# USB-CB.net
KiCad netlist of a schematic drawn in EAGLE
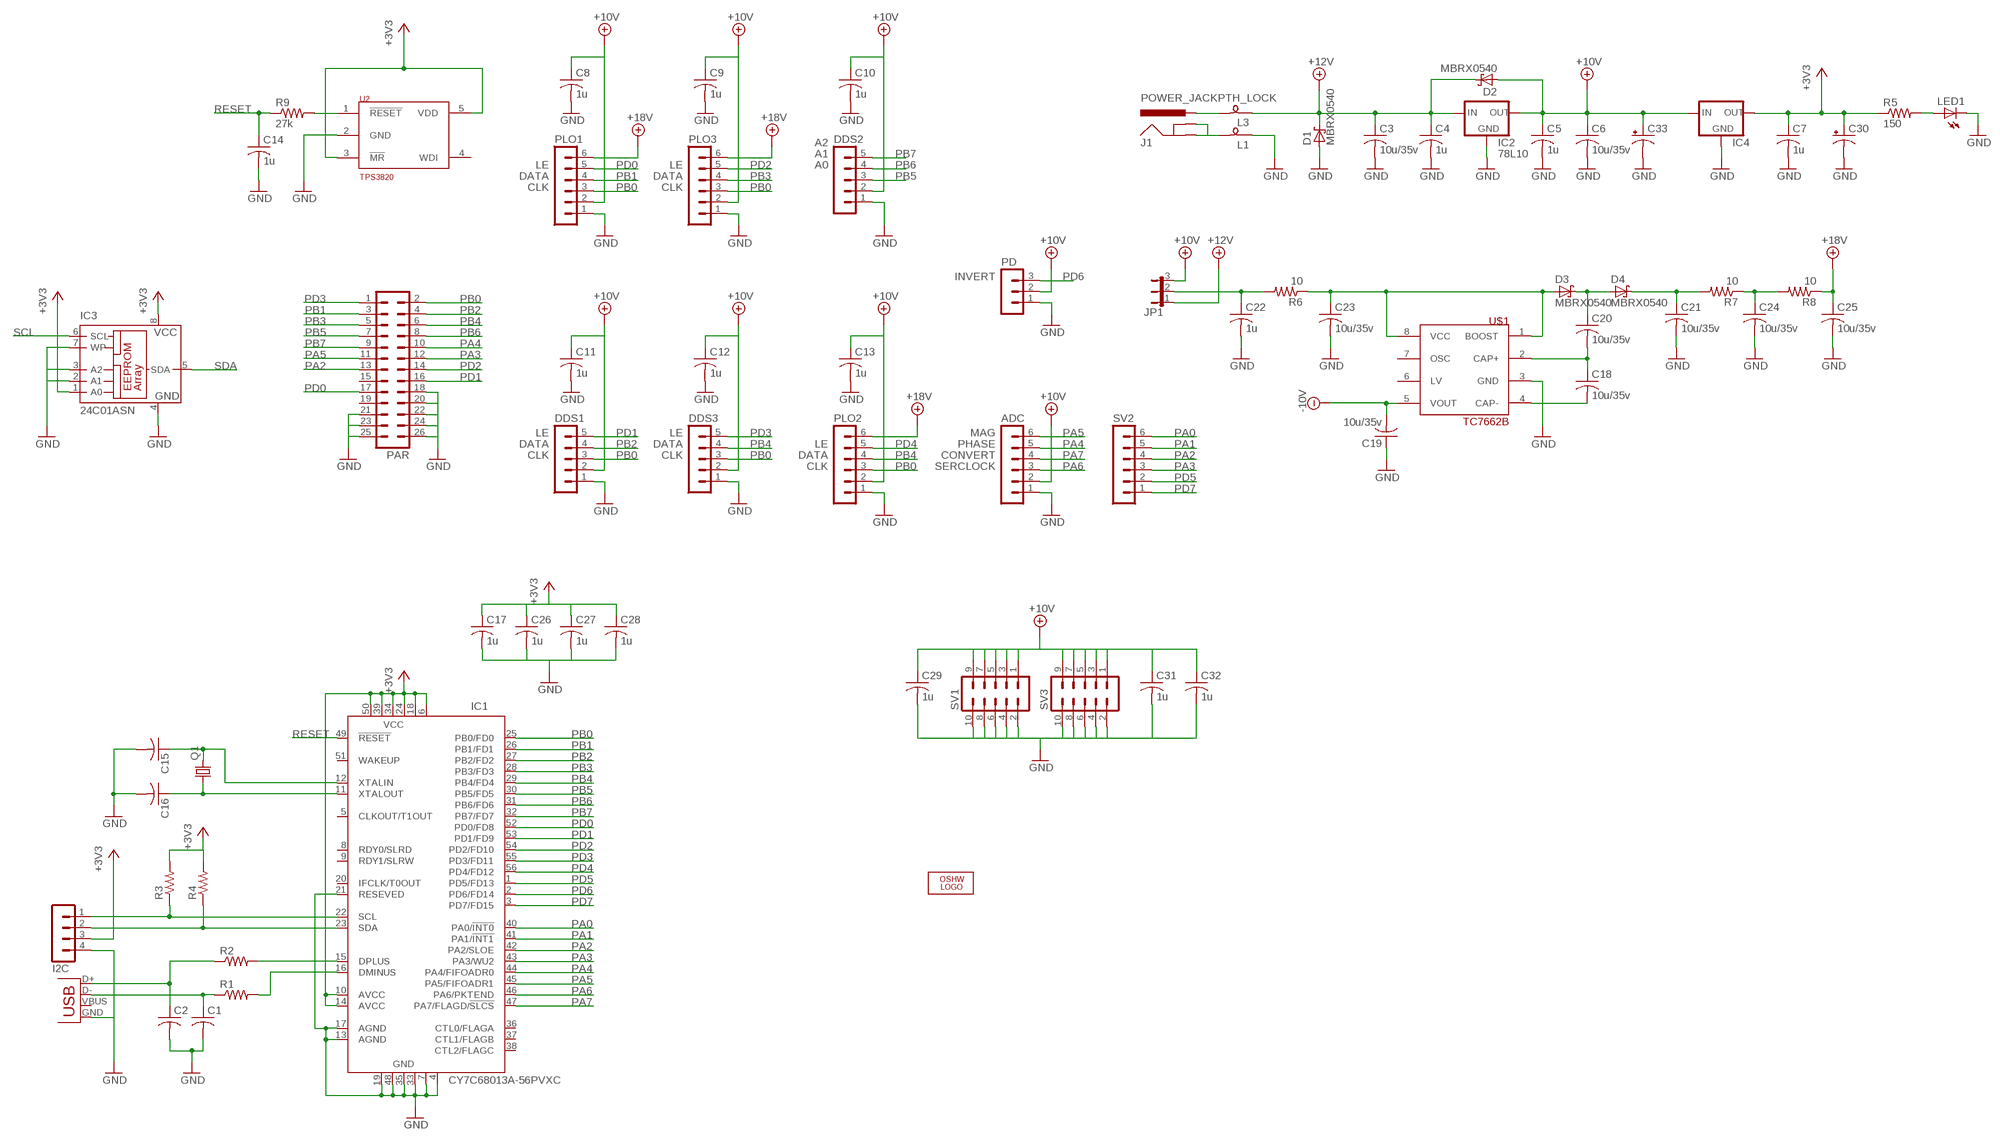
[diagram p0: schematic, sheet 1]

(export (version "E")
  (design (tool "Eeschema 10.0.6"))
  (components
    (comp (ref "ADC")
      (value "MA06-1")
      (footprint "eagle-import:MA06-1")
      (libsource (lib "eagle-import") (part "MA06-1"))
    )
    (comp (ref "C1")
      (value "C-USC0603")
      (footprint "eagle-import:C0603")
      (libsource (lib "eagle-import") (part "C-USC0603"))
    )
    (comp (ref "C2")
      (value "C-USC0603")
      (footprint "eagle-import:C0603")
      (libsource (lib "eagle-import") (part "C-USC0603"))
    )
    (comp (ref "C3")
      (value "10u/35v")
      (footprint "eagle-import:C1206")
      (libsource (lib "eagle-import") (part "C-USC1206"))
    )
    (comp (ref "C4")
      (value "1u")
      (footprint "eagle-import:C0603")
      (libsource (lib "eagle-import") (part "C-USC0603"))
    )
    (comp (ref "C5")
      (value "1u")
      (footprint "eagle-import:C0603")
      (libsource (lib "eagle-import") (part "C-USC0603"))
    )
    (comp (ref "C6")
      (value "10u/35v")
      (footprint "eagle-import:C1206")
      (libsource (lib "eagle-import") (part "C-USC1206"))
    )
    (comp (ref "C7")
      (value "1u")
      (footprint "eagle-import:C0603")
      (libsource (lib "eagle-import") (part "C-USC0603"))
    )
    (comp (ref "C8")
      (value "1u")
      (footprint "eagle-import:C0603")
      (libsource (lib "eagle-import") (part "C-USC0603"))
    )
    (comp (ref "C9")
      (value "1u")
      (footprint "eagle-import:C0603")
      (libsource (lib "eagle-import") (part "C-USC0603"))
    )
    (comp (ref "C10")
      (value "1u")
      (footprint "eagle-import:C0603")
      (libsource (lib "eagle-import") (part "C-USC0603"))
    )
    (comp (ref "C11")
      (value "1u")
      (footprint "eagle-import:C0603")
      (libsource (lib "eagle-import") (part "C-USC0603"))
    )
    (comp (ref "C12")
      (value "1u")
      (footprint "eagle-import:C0603")
      (libsource (lib "eagle-import") (part "C-USC0603"))
    )
    (comp (ref "C13")
      (value "1u")
      (footprint "eagle-import:C0603")
      (libsource (lib "eagle-import") (part "C-USC0603"))
    )
    (comp (ref "C14")
      (value "1u")
      (footprint "eagle-import:C0603")
      (libsource (lib "eagle-import") (part "C-USC0603"))
    )
    (comp (ref "C15")
      (value "C-USC0603")
      (footprint "eagle-import:C0603")
      (libsource (lib "eagle-import") (part "C-USC0603"))
    )
    (comp (ref "C16")
      (value "C-USC0603")
      (footprint "eagle-import:C0603")
      (libsource (lib "eagle-import") (part "C-USC0603"))
    )
    (comp (ref "C17")
      (value "1u")
      (footprint "eagle-import:C0603")
      (libsource (lib "eagle-import") (part "C-USC0603"))
    )
    (comp (ref "C18")
      (value "10u/35v")
      (footprint "eagle-import:C1206")
      (libsource (lib "eagle-import") (part "C-USC1206"))
    )
    (comp (ref "C19")
      (value "10u/35v")
      (footprint "eagle-import:C1206")
      (libsource (lib "eagle-import") (part "C-USC1206"))
    )
    (comp (ref "C20")
      (value "10u/35v")
      (footprint "eagle-import:C1206")
      (libsource (lib "eagle-import") (part "C-USC1206"))
    )
    (comp (ref "C21")
      (value "10u/35v")
      (footprint "eagle-import:C1206")
      (libsource (lib "eagle-import") (part "C-USC1206"))
    )
    (comp (ref "C22")
      (value "1u")
      (footprint "eagle-import:C0603")
      (libsource (lib "eagle-import") (part "C-USC0603"))
    )
    (comp (ref "C23")
      (value "10u/35v")
      (footprint "eagle-import:C1206")
      (libsource (lib "eagle-import") (part "C-USC1206"))
    )
    (comp (ref "C24")
      (value "10u/35v")
      (footprint "eagle-import:C1206")
      (libsource (lib "eagle-import") (part "C-USC1206"))
    )
    (comp (ref "C25")
      (value "10u/35v")
      (footprint "eagle-import:C1206")
      (libsource (lib "eagle-import") (part "C-USC1206"))
    )
    (comp (ref "C26")
      (value "1u")
      (footprint "eagle-import:C0603")
      (libsource (lib "eagle-import") (part "C-USC0603"))
    )
    (comp (ref "C27")
      (value "1u")
      (footprint "eagle-import:C0603")
      (libsource (lib "eagle-import") (part "C-USC0603"))
    )
    (comp (ref "C28")
      (value "1u")
      (footprint "eagle-import:C0603")
      (libsource (lib "eagle-import") (part "C-USC0603"))
    )
    (comp (ref "C29")
      (value "1u")
      (footprint "eagle-import:C0603")
      (libsource (lib "eagle-import") (part "C-USC0603"))
    )
    (comp (ref "C30")
      (value "CPOL-USE2.5-6")
      (footprint "eagle-import:E2,5-6")
      (libsource (lib "eagle-import") (part "CPOL-USE2.5-6"))
    )
    (comp (ref "C31")
      (value "1u")
      (footprint "eagle-import:C0603")
      (libsource (lib "eagle-import") (part "C-USC0603"))
    )
    (comp (ref "C32")
      (value "1u")
      (footprint "eagle-import:C0603")
      (libsource (lib "eagle-import") (part "C-USC0603"))
    )
    (comp (ref "C33")
      (value "CPOL-USE2.5-6")
      (footprint "eagle-import:E2,5-6")
      (libsource (lib "eagle-import") (part "CPOL-USE2.5-6"))
    )
    (comp (ref "D1")
      (value "MBRX0540")
      (footprint "eagle-import:SOD323-R")
      (libsource (lib "eagle-import") (part "MBRX0540"))
    )
    (comp (ref "D2")
      (value "MBRX0540")
      (footprint "eagle-import:SOD323-R")
      (libsource (lib "eagle-import") (part "MBRX0540"))
    )
    (comp (ref "D3")
      (value "MBRX0540")
      (footprint "eagle-import:SOD323-R")
      (libsource (lib "eagle-import") (part "MBRX0540"))
    )
    (comp (ref "D4")
      (value "MBRX0540")
      (footprint "eagle-import:SOD323-R")
      (libsource (lib "eagle-import") (part "MBRX0540"))
    )
    (comp (ref "DDS1")
      (value "MA05-1")
      (footprint "eagle-import:MA05-1")
      (libsource (lib "eagle-import") (part "MA05-1"))
    )
    (comp (ref "DDS2")
      (value "MA05-1")
      (footprint "eagle-import:MA05-1")
      (libsource (lib "eagle-import") (part "MA05-1"))
    )
    (comp (ref "DDS3")
      (value "MA05-1")
      (footprint "eagle-import:MA05-1")
      (libsource (lib "eagle-import") (part "MA05-1"))
    )
    (comp (ref "I2C")
      (value "MA04-1")
      (footprint "eagle-import:MA04-1")
      (libsource (lib "eagle-import") (part "MA04-1"))
    )
    (comp (ref "IC1")
      (value "CY7C68013A-56PVXC")
      (footprint "eagle-import:SSOP56")
      (fields (field (name "MF") "CYPRESS SEMICONDUCTOR CORPORAT"))
      (libsource (lib "eagle-import") (part "CY7C6801A-56PVXC3"))
    )
    (comp (ref "IC2")
      (value "78L10")
      (footprint "eagle-import:78XXS")
      (libsource (lib "eagle-import") (part "78XXS"))
    )
    (comp (ref "IC3")
      (value "24C01ASN")
      (footprint "eagle-import:SO-08")
      (libsource (lib "eagle-import") (part "24CSN01A"))
    )
    (comp (ref "IC4")
      (value "78LXXAC")
      (footprint "eagle-import:SOT89R")
      (libsource (lib "eagle-import") (part "78LXXAC"))
    )
    (comp (ref "J1")
      (value "POWER_JACKPTH_LOCK")
      (footprint "eagle-import:POWER_JACK_PTH_LOCK")
      (libsource (lib "eagle-import") (part "POWER_JACKPTH_LOCK"))
    )
    (comp (ref "JP1")
      (value "JP2E")
      (footprint "eagle-import:JP2")
      (libsource (lib "eagle-import") (part "JP2E"))
    )
    (comp (ref "L1")
      (value "SM-B5")
      (footprint "eagle-import:SM-B5")
      (libsource (lib "eagle-import") (part "SM-B5"))
    )
    (comp (ref "L3")
      (value "SM-B5")
      (footprint "eagle-import:SM-B5")
      (libsource (lib "eagle-import") (part "SM-B5"))
    )
    (comp (ref "LED1")
      (value "LED5MM")
      (footprint "eagle-import:LED5MM")
      (libsource (lib "eagle-import") (part "LED5MM"))
    )
    (comp (ref "LOGO1")
      (value "OSHW_LOGO_FILLX0200-NT")
      (footprint "eagle-import:OSHW_FILLX200_NOTEXT")
      (libsource (lib "eagle-import") (part "OSHW_LOGO_FILLX0200-NT"))
    )
    (comp (ref "PAR")
      (value "MA13-2")
      (footprint "eagle-import:MA13-2")
      (libsource (lib "eagle-import") (part "MA13-2"))
    )
    (comp (ref "PD")
      (value "MA03-1")
      (footprint "eagle-import:MA03-1")
      (libsource (lib "eagle-import") (part "MA03-1"))
    )
    (comp (ref "PLO1")
      (value "MA06-1")
      (footprint "eagle-import:MA06-1")
      (libsource (lib "eagle-import") (part "MA06-1"))
    )
    (comp (ref "PLO2")
      (value "MA06-1")
      (footprint "eagle-import:MA06-1")
      (libsource (lib "eagle-import") (part "MA06-1"))
    )
    (comp (ref "PLO3")
      (value "MA06-1")
      (footprint "eagle-import:MA06-1")
      (libsource (lib "eagle-import") (part "MA06-1"))
    )
    (comp (ref "Q1")
      (value "CRYSTALHC49S")
      (footprint "eagle-import:HC49_S")
      (libsource (lib "eagle-import") (part "CRYSTALHC49S"))
    )
    (comp (ref "R1")
      (value "R-US_R0603")
      (footprint "eagle-import:R0603")
      (libsource (lib "eagle-import") (part "R-US_R0603"))
    )
    (comp (ref "R2")
      (value "R-US_R0603")
      (footprint "eagle-import:R0603")
      (libsource (lib "eagle-import") (part "R-US_R0603"))
    )
    (comp (ref "R3")
      (value "R-US_R0603")
      (footprint "eagle-import:R0603")
      (libsource (lib "eagle-import") (part "R-US_R0603"))
    )
    (comp (ref "R4")
      (value "R-US_R0603")
      (footprint "eagle-import:R0603")
      (libsource (lib "eagle-import") (part "R-US_R0603"))
    )
    (comp (ref "R5")
      (value "150")
      (footprint "eagle-import:R0603")
      (libsource (lib "eagle-import") (part "R-US_R0603"))
    )
    (comp (ref "R6")
      (value "10")
      (footprint "eagle-import:R0603")
      (libsource (lib "eagle-import") (part "R-US_R0603"))
    )
    (comp (ref "R7")
      (value "10")
      (footprint "eagle-import:R0603")
      (libsource (lib "eagle-import") (part "R-US_R0603"))
    )
    (comp (ref "R8")
      (value "10")
      (footprint "eagle-import:R0603")
      (libsource (lib "eagle-import") (part "R-US_R0603"))
    )
    (comp (ref "R9")
      (value "27k")
      (footprint "eagle-import:R0603")
      (libsource (lib "eagle-import") (part "R-US_R0603"))
    )
    (comp (ref "SV1")
      (value "MA05-2PIN")
      (footprint "eagle-import:MA05-2")
      (libsource (lib "eagle-import") (part "MA05-2PIN"))
    )
    (comp (ref "SV2")
      (value "MA06-1")
      (footprint "eagle-import:MA06-1")
      (libsource (lib "eagle-import") (part "MA06-1"))
    )
    (comp (ref "SV3")
      (value "MA05-2PIN")
      (footprint "eagle-import:MA05-2")
      (libsource (lib "eagle-import") (part "MA05-2PIN"))
    )
    (comp (ref "U$1")
      (value "TC7662B")
      (footprint "eagle-import:SO-08")
      (libsource (lib "eagle-import") (part "TC7662B"))
    )
    (comp (ref "U2")
      (value "TPS3820")
      (footprint "eagle-import:SC74_INFINEON")
      (libsource (lib "eagle-import") (part "TPS3820"))
    )
    (comp (ref "X1")
      (value "USBSMD")
      (footprint "eagle-import:USB-MINIB")
      (libsource (lib "eagle-import") (part "USBSMD"))
    )
  )
  (nets
    (net (code "1") (name "+3V3") (class "Default")
      (node (ref "C17") (pin "1") (pinfunction "1_1") (pintype "passive"))
      (node (ref "C26") (pin "1") (pinfunction "1_1") (pintype "passive"))
      (node (ref "C27") (pin "1") (pinfunction "1_1") (pintype "passive"))
      (node (ref "C28") (pin "1") (pinfunction "1_1") (pintype "passive"))
      (node (ref "C30") (pin "+") (pinfunction "+_+") (pintype "passive"))
      (node (ref "C7") (pin "1") (pinfunction "1_1") (pintype "passive"))
      (node (ref "I2C") (pin "3") (pinfunction "3_3") (pintype "passive"))
      (node (ref "IC1") (pin "10") (pinfunction "AVCC_10") (pintype "input"))
      (node (ref "IC1") (pin "14") (pinfunction "AVCC_14") (pintype "input"))
      (node (ref "IC1") (pin "18") (pinfunction "VCC_18") (pintype "input"))
      (node (ref "IC1") (pin "24") (pinfunction "VCC_24") (pintype "input"))
      (node (ref "IC1") (pin "34") (pinfunction "VCC_34") (pintype "input"))
      (node (ref "IC1") (pin "39") (pinfunction "VCC_39") (pintype "input"))
      (node (ref "IC1") (pin "50") (pinfunction "VCC_50") (pintype "input"))
      (node (ref "IC1") (pin "6") (pinfunction "VCC_6") (pintype "input"))
      (node (ref "IC3") (pin "1") (pinfunction "A0_1") (pintype "input"))
      (node (ref "IC3") (pin "8") (pinfunction "VCC_8") (pintype "power_in"))
      (node (ref "IC4") (pin "3") (pinfunction "OUT_3") (pintype "passive"))
      (node (ref "R3") (pin "2") (pinfunction "2_2") (pintype "passive"))
      (node (ref "R4") (pin "2") (pinfunction "2_2") (pintype "passive"))
      (node (ref "R5") (pin "1") (pinfunction "1_1") (pintype "passive"))
      (node (ref "U2") (pin "3") (pinfunction "~{MR}_3") (pintype "bidirectional"))
      (node (ref "U2") (pin "5") (pinfunction "VDD_5") (pintype "bidirectional"))
    )
    (net (code "2") (name "+10V") (class "Default")
      (node (ref "ADC") (pin "2") (pinfunction "2_2") (pintype "passive"))
      (node (ref "C10") (pin "1") (pinfunction "1_1") (pintype "passive"))
      (node (ref "C11") (pin "1") (pinfunction "1_1") (pintype "passive"))
      (node (ref "C12") (pin "1") (pinfunction "1_1") (pintype "passive"))
      (node (ref "C13") (pin "1") (pinfunction "1_1") (pintype "passive"))
      (node (ref "C29") (pin "1") (pinfunction "1_1") (pintype "passive"))
      (node (ref "C31") (pin "1") (pinfunction "1_1") (pintype "passive"))
      (node (ref "C32") (pin "1") (pinfunction "1_1") (pintype "passive"))
      (node (ref "C33") (pin "+") (pinfunction "+_+") (pintype "passive"))
      (node (ref "C5") (pin "1") (pinfunction "1_1") (pintype "passive"))
      (node (ref "C6") (pin "1") (pinfunction "1_1") (pintype "passive"))
      (node (ref "C8") (pin "1") (pinfunction "1_1") (pintype "passive"))
      (node (ref "C9") (pin "1") (pinfunction "1_1") (pintype "passive"))
      (node (ref "D2") (pin "A") (pinfunction "A_A") (pintype "passive"))
      (node (ref "DDS1") (pin "2") (pinfunction "2_2") (pintype "passive"))
      (node (ref "DDS2") (pin "2") (pinfunction "2_2") (pintype "passive"))
      (node (ref "DDS3") (pin "2") (pinfunction "2_2") (pintype "passive"))
      (node (ref "IC2") (pin "OUT") (pinfunction "OUT_OUT") (pintype "passive"))
      (node (ref "IC4") (pin "1") (pinfunction "IN_1") (pintype "input"))
      (node (ref "JP1") (pin "3") (pinfunction "3_3") (pintype "passive"))
      (node (ref "PD") (pin "2") (pinfunction "2_2") (pintype "passive"))
      (node (ref "PLO1") (pin "2") (pinfunction "2_2") (pintype "passive"))
      (node (ref "PLO2") (pin "2") (pinfunction "2_2") (pintype "passive"))
      (node (ref "PLO3") (pin "2") (pinfunction "2_2") (pintype "passive"))
      (node (ref "SV1") (pin "1") (pinfunction "1_1") (pintype "passive"))
      (node (ref "SV1") (pin "3") (pinfunction "3_3") (pintype "passive"))
      (node (ref "SV1") (pin "5") (pinfunction "5_5") (pintype "passive"))
      (node (ref "SV1") (pin "7") (pinfunction "7_7") (pintype "passive"))
      (node (ref "SV1") (pin "9") (pinfunction "9_9") (pintype "passive"))
      (node (ref "SV3") (pin "1") (pinfunction "1_1") (pintype "passive"))
      (node (ref "SV3") (pin "3") (pinfunction "3_3") (pintype "passive"))
      (node (ref "SV3") (pin "5") (pinfunction "5_5") (pintype "passive"))
      (node (ref "SV3") (pin "7") (pinfunction "7_7") (pintype "passive"))
      (node (ref "SV3") (pin "9") (pinfunction "9_9") (pintype "passive"))
    )
    (net (code "3") (name "+12V") (class "Default")
      (node (ref "C3") (pin "1") (pinfunction "1_1") (pintype "passive"))
      (node (ref "C4") (pin "1") (pinfunction "1_1") (pintype "passive"))
      (node (ref "D1") (pin "C") (pinfunction "C_C") (pintype "passive"))
      (node (ref "D2") (pin "C") (pinfunction "C_C") (pintype "passive"))
      (node (ref "IC2") (pin "IN") (pinfunction "IN_IN") (pintype "input"))
      (node (ref "JP1") (pin "1") (pinfunction "1_1") (pintype "passive"))
      (node (ref "L3") (pin "1") (pinfunction "1_1") (pintype "passive"))
    )
    (net (code "4") (name "+18V") (class "Default")
      (node (ref "C25") (pin "1") (pinfunction "1_1") (pintype "passive"))
      (node (ref "PLO1") (pin "6") (pinfunction "6_6") (pintype "passive"))
      (node (ref "PLO2") (pin "6") (pinfunction "6_6") (pintype "passive"))
      (node (ref "PLO3") (pin "6") (pinfunction "6_6") (pintype "passive"))
      (node (ref "R8") (pin "1") (pinfunction "1_1") (pintype "passive"))
    )
    (net (code "5") (name "-10V") (class "Default")
      (node (ref "C19") (pin "2") (pinfunction "2_2") (pintype "passive"))
      (node (ref "U$1") (pin "5") (pinfunction "VOUT_5") (pintype "bidirectional"))
    )
    (net (code "6") (name "/PA0") (class "Default")
      (node (ref "IC1") (pin "40") (pinfunction "PA0/~{INT0}_40") (pintype "bidirectional"))
      (node (ref "SV2") (pin "6") (pinfunction "6_6") (pintype "passive"))
    )
    (net (code "7") (name "/PA1") (class "Default")
      (node (ref "IC1") (pin "41") (pinfunction "PA1/~{INT1}_41") (pintype "bidirectional"))
      (node (ref "SV2") (pin "5") (pinfunction "5_5") (pintype "passive"))
    )
    (net (code "8") (name "/PA2") (class "Default")
      (node (ref "IC1") (pin "42") (pinfunction "PA2/SLOE_42") (pintype "bidirectional"))
      (node (ref "PAR") (pin "13") (pinfunction "13_13") (pintype "passive"))
      (node (ref "SV2") (pin "4") (pinfunction "4_4") (pintype "passive"))
    )
    (net (code "9") (name "/PA3") (class "Default")
      (node (ref "IC1") (pin "43") (pinfunction "PA3/WU2_43") (pintype "bidirectional"))
      (node (ref "PAR") (pin "12") (pinfunction "12_12") (pintype "passive"))
      (node (ref "SV2") (pin "3") (pinfunction "3_3") (pintype "passive"))
    )
    (net (code "10") (name "/PA4") (class "Default")
      (node (ref "ADC") (pin "5") (pinfunction "5_5") (pintype "passive"))
      (node (ref "IC1") (pin "44") (pinfunction "PA4/FIFOADR0_44") (pintype "bidirectional"))
      (node (ref "PAR") (pin "10") (pinfunction "10_10") (pintype "passive"))
    )
    (net (code "11") (name "/PA5") (class "Default")
      (node (ref "ADC") (pin "6") (pinfunction "6_6") (pintype "passive"))
      (node (ref "IC1") (pin "45") (pinfunction "PA5/FIFOADR1_45") (pintype "bidirectional"))
      (node (ref "PAR") (pin "11") (pinfunction "11_11") (pintype "passive"))
    )
    (net (code "12") (name "/PA6") (class "Default")
      (node (ref "ADC") (pin "3") (pinfunction "3_3") (pintype "passive"))
      (node (ref "IC1") (pin "46") (pinfunction "PA6/PKTEND_46") (pintype "bidirectional"))
    )
    (net (code "13") (name "/PA7") (class "Default")
      (node (ref "ADC") (pin "4") (pinfunction "4_4") (pintype "passive"))
      (node (ref "IC1") (pin "47") (pinfunction "PA7/FLAGD/~{SLCS}_47") (pintype "bidirectional"))
    )
    (net (code "14") (name "/PB0") (class "Default")
      (node (ref "DDS1") (pin "3") (pinfunction "3_3") (pintype "passive"))
      (node (ref "DDS3") (pin "3") (pinfunction "3_3") (pintype "passive"))
      (node (ref "IC1") (pin "25") (pinfunction "PB0/FD0_25") (pintype "bidirectional"))
      (node (ref "PAR") (pin "2") (pinfunction "2_2") (pintype "passive"))
      (node (ref "PLO1") (pin "3") (pinfunction "3_3") (pintype "passive"))
      (node (ref "PLO2") (pin "3") (pinfunction "3_3") (pintype "passive"))
      (node (ref "PLO3") (pin "3") (pinfunction "3_3") (pintype "passive"))
    )
    (net (code "15") (name "/PB1") (class "Default")
      (node (ref "IC1") (pin "26") (pinfunction "PB1/FD1_26") (pintype "bidirectional"))
      (node (ref "PAR") (pin "3") (pinfunction "3_3") (pintype "passive"))
      (node (ref "PLO1") (pin "4") (pinfunction "4_4") (pintype "passive"))
    )
    (net (code "16") (name "/PB2") (class "Default")
      (node (ref "DDS1") (pin "4") (pinfunction "4_4") (pintype "passive"))
      (node (ref "IC1") (pin "27") (pinfunction "PB2/FD2_27") (pintype "bidirectional"))
      (node (ref "PAR") (pin "4") (pinfunction "4_4") (pintype "passive"))
    )
    (net (code "17") (name "/PB3") (class "Default")
      (node (ref "IC1") (pin "28") (pinfunction "PB3/FD3_28") (pintype "bidirectional"))
      (node (ref "PAR") (pin "5") (pinfunction "5_5") (pintype "passive"))
      (node (ref "PLO3") (pin "4") (pinfunction "4_4") (pintype "passive"))
    )
    (net (code "18") (name "/PB4") (class "Default")
      (node (ref "DDS3") (pin "4") (pinfunction "4_4") (pintype "passive"))
      (node (ref "IC1") (pin "29") (pinfunction "PB4/FD4_29") (pintype "bidirectional"))
      (node (ref "PAR") (pin "6") (pinfunction "6_6") (pintype "passive"))
      (node (ref "PLO2") (pin "4") (pinfunction "4_4") (pintype "passive"))
    )
    (net (code "19") (name "/PB5") (class "Default")
      (node (ref "DDS2") (pin "3") (pinfunction "3_3") (pintype "passive"))
      (node (ref "IC1") (pin "30") (pinfunction "PB5/FD5_30") (pintype "bidirectional"))
      (node (ref "PAR") (pin "7") (pinfunction "7_7") (pintype "passive"))
    )
    (net (code "20") (name "/PB6") (class "Default")
      (node (ref "DDS2") (pin "4") (pinfunction "4_4") (pintype "passive"))
      (node (ref "IC1") (pin "31") (pinfunction "PB6/FD6_31") (pintype "bidirectional"))
      (node (ref "PAR") (pin "8") (pinfunction "8_8") (pintype "passive"))
    )
    (net (code "21") (name "/PB7") (class "Default")
      (node (ref "DDS2") (pin "5") (pinfunction "5_5") (pintype "passive"))
      (node (ref "IC1") (pin "32") (pinfunction "PB7/FD7_32") (pintype "bidirectional"))
      (node (ref "PAR") (pin "9") (pinfunction "9_9") (pintype "passive"))
    )
    (net (code "22") (name "/PD0") (class "Default")
      (node (ref "IC1") (pin "52") (pinfunction "PD0/FD8_52") (pintype "bidirectional"))
      (node (ref "PAR") (pin "17") (pinfunction "17_17") (pintype "passive"))
      (node (ref "PLO1") (pin "5") (pinfunction "5_5") (pintype "passive"))
    )
    (net (code "23") (name "/PD1") (class "Default")
      (node (ref "DDS1") (pin "5") (pinfunction "5_5") (pintype "passive"))
      (node (ref "IC1") (pin "53") (pinfunction "PD1/FD9_53") (pintype "bidirectional"))
      (node (ref "PAR") (pin "16") (pinfunction "16_16") (pintype "passive"))
    )
    (net (code "24") (name "/PD2") (class "Default")
      (node (ref "IC1") (pin "54") (pinfunction "PD2/FD10_54") (pintype "bidirectional"))
      (node (ref "PAR") (pin "14") (pinfunction "14_14") (pintype "passive"))
      (node (ref "PLO3") (pin "5") (pinfunction "5_5") (pintype "passive"))
    )
    (net (code "25") (name "/PD3") (class "Default")
      (node (ref "DDS3") (pin "5") (pinfunction "5_5") (pintype "passive"))
      (node (ref "IC1") (pin "55") (pinfunction "PD3/FD11_55") (pintype "bidirectional"))
      (node (ref "PAR") (pin "1") (pinfunction "1_1") (pintype "passive"))
    )
    (net (code "26") (name "/PD4") (class "Default")
      (node (ref "IC1") (pin "56") (pinfunction "PD4/FD12_56") (pintype "bidirectional"))
      (node (ref "PLO2") (pin "5") (pinfunction "5_5") (pintype "passive"))
    )
    (net (code "27") (name "/PD5") (class "Default")
      (node (ref "IC1") (pin "1") (pinfunction "PD5/FD13_1") (pintype "bidirectional"))
      (node (ref "SV2") (pin "2") (pinfunction "2_2") (pintype "passive"))
    )
    (net (code "28") (name "/PD6") (class "Default")
      (node (ref "IC1") (pin "2") (pinfunction "PD6/FD14_2") (pintype "bidirectional"))
      (node (ref "PD") (pin "3") (pinfunction "3_3") (pintype "passive"))
    )
    (net (code "29") (name "/PD7") (class "Default")
      (node (ref "IC1") (pin "3") (pinfunction "PD7/FD15_3") (pintype "bidirectional"))
      (node (ref "SV2") (pin "1") (pinfunction "1_1") (pintype "passive"))
    )
    (net (code "30") (name "/RESET") (class "Default")
      (node (ref "C14") (pin "1") (pinfunction "1_1") (pintype "passive"))
      (node (ref "IC1") (pin "49") (pinfunction "~{RESET}_49") (pintype "input"))
      (node (ref "R9") (pin "1") (pinfunction "1_1") (pintype "passive"))
    )
    (net (code "31") (name "/SCL") (class "Default")
      (node (ref "I2C") (pin "1") (pinfunction "1_1") (pintype "passive"))
      (node (ref "IC1") (pin "22") (pinfunction "SCL_22") (pintype "output"))
      (node (ref "IC3") (pin "6") (pinfunction "SCL_6") (pintype "input"))
      (node (ref "R3") (pin "1") (pinfunction "1_1") (pintype "passive"))
    )
    (net (code "32") (name "/SDA") (class "Default")
      (node (ref "I2C") (pin "2") (pinfunction "2_2") (pintype "passive"))
      (node (ref "IC1") (pin "23") (pinfunction "SDA_23") (pintype "bidirectional"))
      (node (ref "IC3") (pin "5") (pinfunction "SDA_5") (pintype "bidirectional"))
      (node (ref "R4") (pin "1") (pinfunction "1_1") (pintype "passive"))
    )
    (net (code "33") (name "GND") (class "Default")
      (node (ref "ADC") (pin "1") (pinfunction "1_1") (pintype "passive"))
      (node (ref "C1") (pin "2") (pinfunction "2_2") (pintype "passive"))
      (node (ref "C10") (pin "2") (pinfunction "2_2") (pintype "passive"))
      (node (ref "C11") (pin "2") (pinfunction "2_2") (pintype "passive"))
      (node (ref "C12") (pin "2") (pinfunction "2_2") (pintype "passive"))
      (node (ref "C13") (pin "2") (pinfunction "2_2") (pintype "passive"))
      (node (ref "C14") (pin "2") (pinfunction "2_2") (pintype "passive"))
      (node (ref "C15") (pin "2") (pinfunction "2_2") (pintype "passive"))
      (node (ref "C16") (pin "2") (pinfunction "2_2") (pintype "passive"))
      (node (ref "C17") (pin "2") (pinfunction "2_2") (pintype "passive"))
      (node (ref "C19") (pin "1") (pinfunction "1_1") (pintype "passive"))
      (node (ref "C2") (pin "2") (pinfunction "2_2") (pintype "passive"))
      (node (ref "C21") (pin "2") (pinfunction "2_2") (pintype "passive"))
      (node (ref "C22") (pin "2") (pinfunction "2_2") (pintype "passive"))
      (node (ref "C23") (pin "2") (pinfunction "2_2") (pintype "passive"))
      (node (ref "C24") (pin "2") (pinfunction "2_2") (pintype "passive"))
      (node (ref "C25") (pin "2") (pinfunction "2_2") (pintype "passive"))
      (node (ref "C26") (pin "2") (pinfunction "2_2") (pintype "passive"))
      (node (ref "C27") (pin "2") (pinfunction "2_2") (pintype "passive"))
      (node (ref "C28") (pin "2") (pinfunction "2_2") (pintype "passive"))
      (node (ref "C29") (pin "2") (pinfunction "2_2") (pintype "passive"))
      (node (ref "C3") (pin "2") (pinfunction "2_2") (pintype "passive"))
      (node (ref "C30") (pin "-") (pinfunction "-_-") (pintype "passive"))
      (node (ref "C31") (pin "2") (pinfunction "2_2") (pintype "passive"))
      (node (ref "C32") (pin "2") (pinfunction "2_2") (pintype "passive"))
      (node (ref "C33") (pin "-") (pinfunction "-_-") (pintype "passive"))
      (node (ref "C4") (pin "2") (pinfunction "2_2") (pintype "passive"))
      (node (ref "C5") (pin "2") (pinfunction "2_2") (pintype "passive"))
      (node (ref "C6") (pin "2") (pinfunction "2_2") (pintype "passive"))
      (node (ref "C7") (pin "2") (pinfunction "2_2") (pintype "passive"))
      (node (ref "C8") (pin "2") (pinfunction "2_2") (pintype "passive"))
      (node (ref "C9") (pin "2") (pinfunction "2_2") (pintype "passive"))
      (node (ref "D1") (pin "A") (pinfunction "A_A") (pintype "passive"))
      (node (ref "DDS1") (pin "1") (pinfunction "1_1") (pintype "passive"))
      (node (ref "DDS2") (pin "1") (pinfunction "1_1") (pintype "passive"))
      (node (ref "DDS3") (pin "1") (pinfunction "1_1") (pintype "passive"))
      (node (ref "I2C") (pin "4") (pinfunction "4_4") (pintype "passive"))
      (node (ref "IC1") (pin "13") (pinfunction "AGND_13") (pintype "input"))
      (node (ref "IC1") (pin "17") (pinfunction "AGND_17") (pintype "input"))
      (node (ref "IC1") (pin "19") (pinfunction "GND_19") (pintype "input"))
      (node (ref "IC1") (pin "21") (pinfunction "RESEVED_21") (pintype "input"))
      (node (ref "IC1") (pin "33") (pinfunction "GND_33") (pintype "input"))
      (node (ref "IC1") (pin "35") (pinfunction "GND_35") (pintype "input"))
      (node (ref "IC1") (pin "4") (pinfunction "GND_4") (pintype "input"))
      (node (ref "IC1") (pin "48") (pinfunction "GND_48") (pintype "input"))
      (node (ref "IC1") (pin "7") (pinfunction "GND_7") (pintype "input"))
      (node (ref "IC2") (pin "GND") (pinfunction "GND_GND") (pintype "input"))
      (node (ref "IC3") (pin "2") (pinfunction "A1_2") (pintype "input"))
      (node (ref "IC3") (pin "3") (pinfunction "A2_3") (pintype "input"))
      (node (ref "IC3") (pin "4") (pinfunction "GND_4") (pintype "power_in"))
      (node (ref "IC3") (pin "7") (pinfunction "WP_7") (pintype "input"))
      (node (ref "IC4") (pin "2") (pinfunction "GND_2") (pintype "input"))
      (node (ref "L1") (pin "1") (pinfunction "1_1") (pintype "passive"))
      (node (ref "LED1") (pin "K") (pinfunction "C_K") (pintype "passive"))
      (node (ref "PAR") (pin "18") (pinfunction "18_18") (pintype "passive"))
      (node (ref "PAR") (pin "20") (pinfunction "20_20") (pintype "passive"))
      (node (ref "PAR") (pin "21") (pinfunction "21_21") (pintype "passive"))
      (node (ref "PAR") (pin "22") (pinfunction "22_22") (pintype "passive"))
      (node (ref "PAR") (pin "23") (pinfunction "23_23") (pintype "passive"))
      (node (ref "PAR") (pin "24") (pinfunction "24_24") (pintype "passive"))
      (node (ref "PAR") (pin "25") (pinfunction "25_25") (pintype "passive"))
      (node (ref "PAR") (pin "26") (pinfunction "26_26") (pintype "passive"))
      (node (ref "PD") (pin "1") (pinfunction "1_1") (pintype "passive"))
      (node (ref "PLO1") (pin "1") (pinfunction "1_1") (pintype "passive"))
      (node (ref "PLO2") (pin "1") (pinfunction "1_1") (pintype "passive"))
      (node (ref "PLO3") (pin "1") (pinfunction "1_1") (pintype "passive"))
      (node (ref "SV1") (pin "10") (pinfunction "10_10") (pintype "passive"))
      (node (ref "SV1") (pin "2") (pinfunction "2_2") (pintype "passive"))
      (node (ref "SV1") (pin "4") (pinfunction "4_4") (pintype "passive"))
      (node (ref "SV1") (pin "6") (pinfunction "6_6") (pintype "passive"))
      (node (ref "SV1") (pin "8") (pinfunction "8_8") (pintype "passive"))
      (node (ref "SV3") (pin "10") (pinfunction "10_10") (pintype "passive"))
      (node (ref "SV3") (pin "2") (pinfunction "2_2") (pintype "passive"))
      (node (ref "SV3") (pin "4") (pinfunction "4_4") (pintype "passive"))
      (node (ref "SV3") (pin "6") (pinfunction "6_6") (pintype "passive"))
      (node (ref "SV3") (pin "8") (pinfunction "8_8") (pintype "passive"))
      (node (ref "U$1") (pin "3") (pinfunction "GND_3") (pintype "bidirectional"))
      (node (ref "U2") (pin "2") (pinfunction "GND_2") (pintype "bidirectional"))
      (node (ref "X1") (pin "GND") (pinfunction "GND_GND") (pintype "bidirectional"))
    )
    (net (code "34") (name "Net-(C1-Pad1)") (class "Default")
      (node (ref "C1") (pin "1") (pinfunction "1_1") (pintype "passive"))
      (node (ref "R1") (pin "1") (pinfunction "1_1") (pintype "passive"))
      (node (ref "X1") (pin "D-") (pinfunction "D-_D-") (pintype "bidirectional"))
    )
    (net (code "35") (name "Net-(C2-Pad1)") (class "Default")
      (node (ref "C2") (pin "1") (pinfunction "1_1") (pintype "passive"))
      (node (ref "R2") (pin "1") (pinfunction "1_1") (pintype "passive"))
      (node (ref "X1") (pin "D+") (pinfunction "D+_D+") (pintype "bidirectional"))
    )
    (net (code "36") (name "Net-(C20-Pad1)") (class "Default")
      (node (ref "C20") (pin "1") (pinfunction "1_1") (pintype "passive"))
      (node (ref "D3") (pin "C") (pinfunction "C_C") (pintype "passive"))
      (node (ref "D4") (pin "A") (pinfunction "A_A") (pintype "passive"))
    )
    (net (code "37") (name "Net-(C21-Pad1)") (class "Default")
      (node (ref "C21") (pin "1") (pinfunction "1_1") (pintype "passive"))
      (node (ref "D4") (pin "C") (pinfunction "C_C") (pintype "passive"))
      (node (ref "R7") (pin "2") (pinfunction "2_2") (pintype "passive"))
    )
    (net (code "38") (name "Net-(C22-Pad1)") (class "Default")
      (node (ref "C22") (pin "1") (pinfunction "1_1") (pintype "passive"))
      (node (ref "JP1") (pin "2") (pinfunction "2_2") (pintype "passive"))
      (node (ref "R6") (pin "2") (pinfunction "2_2") (pintype "passive"))
    )
    (net (code "39") (name "Net-(C24-Pad1)") (class "Default")
      (node (ref "C24") (pin "1") (pinfunction "1_1") (pintype "passive"))
      (node (ref "R7") (pin "1") (pinfunction "1_1") (pintype "passive"))
      (node (ref "R8") (pin "2") (pinfunction "2_2") (pintype "passive"))
    )
    (net (code "40") (name "Net-(IC1-DMINUS)") (class "Default")
      (node (ref "IC1") (pin "16") (pinfunction "DMINUS_16") (pintype "bidirectional"))
      (node (ref "R1") (pin "2") (pinfunction "2_2") (pintype "passive"))
    )
    (net (code "41") (name "Net-(IC1-DPLUS)") (class "Default")
      (node (ref "IC1") (pin "15") (pinfunction "DPLUS_15") (pintype "bidirectional"))
      (node (ref "R2") (pin "2") (pinfunction "2_2") (pintype "passive"))
    )
    (net (code "42") (name "Net-(IC1-XTALIN)") (class "Default")
      (node (ref "C15") (pin "1") (pinfunction "1_1") (pintype "passive"))
      (node (ref "IC1") (pin "12") (pinfunction "XTALIN_12") (pintype "input"))
      (node (ref "Q1") (pin "2") (pinfunction "2_2") (pintype "passive"))
    )
    (net (code "43") (name "Net-(IC1-XTALOUT)") (class "Default")
      (node (ref "C16") (pin "1") (pinfunction "1_1") (pintype "passive"))
      (node (ref "IC1") (pin "11") (pinfunction "XTALOUT_11") (pintype "input"))
      (node (ref "Q1") (pin "1") (pinfunction "1_1") (pintype "passive"))
    )
    (net (code "44") (name "Net-(J1-PadGND)") (class "Default")
      (node (ref "J1") (pin "GND") (pinfunction "GND_GND") (pintype "bidirectional"))
      (node (ref "L1") (pin "2") (pinfunction "2_2") (pintype "passive"))
    )
    (net (code "45") (name "Net-(J1-PadPWR)") (class "Default")
      (node (ref "J1") (pin "PWR") (pinfunction "PWR_PWR") (pintype "bidirectional"))
      (node (ref "L3") (pin "2") (pinfunction "2_2") (pintype "passive"))
    )
    (net (code "46") (name "Net-(LED1-PadA)") (class "Default")
      (node (ref "LED1") (pin "A") (pinfunction "A_A") (pintype "passive"))
      (node (ref "R5") (pin "2") (pinfunction "2_2") (pintype "passive"))
    )
    (net (code "47") (name "Net-(U$1-BOOST)") (class "Default")
      (node (ref "C23") (pin "1") (pinfunction "1_1") (pintype "passive"))
      (node (ref "D3") (pin "A") (pinfunction "A_A") (pintype "passive"))
      (node (ref "R6") (pin "1") (pinfunction "1_1") (pintype "passive"))
      (node (ref "U$1") (pin "1") (pinfunction "BOOST_1") (pintype "bidirectional"))
      (node (ref "U$1") (pin "8") (pinfunction "VCC_8") (pintype "bidirectional"))
    )
    (net (code "48") (name "Net-(U$1-CAP+)") (class "Default")
      (node (ref "C18") (pin "1") (pinfunction "1_1") (pintype "passive"))
      (node (ref "C20") (pin "2") (pinfunction "2_2") (pintype "passive"))
      (node (ref "U$1") (pin "2") (pinfunction "CAP+_2") (pintype "bidirectional"))
    )
    (net (code "49") (name "Net-(U$1-CAP-)") (class "Default")
      (node (ref "C18") (pin "2") (pinfunction "2_2") (pintype "passive"))
      (node (ref "U$1") (pin "4") (pinfunction "CAP-_4") (pintype "bidirectional"))
    )
    (net (code "50") (name "Net-(U2-~{RESET})") (class "Default")
      (node (ref "R9") (pin "2") (pinfunction "2_2") (pintype "passive"))
      (node (ref "U2") (pin "1") (pinfunction "~{RESET}_1") (pintype "bidirectional"))
    )
    (net (code "51") (name "unconnected-(IC1-CLKOUT{slash}T1OUT-Pad5)") (class "Default")
      (node (ref "IC1") (pin "5") (pinfunction "CLKOUT/T1OUT_5") (pintype "input"))
    )
    (net (code "52") (name "unconnected-(IC1-CTL0{slash}FLAGA-Pad36)") (class "Default")
      (node (ref "IC1") (pin "36") (pinfunction "CTL0/FLAGA_36") (pintype "output"))
    )
    (net (code "53") (name "unconnected-(IC1-CTL1{slash}FLAGB-Pad37)") (class "Default")
      (node (ref "IC1") (pin "37") (pinfunction "CTL1/FLAGB_37") (pintype "output"))
    )
    (net (code "54") (name "unconnected-(IC1-CTL2{slash}FLAGC-Pad38)") (class "Default")
      (node (ref "IC1") (pin "38") (pinfunction "CTL2/FLAGC_38") (pintype "output"))
    )
    (net (code "55") (name "unconnected-(IC1-IFCLK{slash}T0OUT-Pad20)") (class "Default")
      (node (ref "IC1") (pin "20") (pinfunction "IFCLK/T0OUT_20") (pintype "bidirectional"))
    )
    (net (code "56") (name "unconnected-(IC1-RDY0{slash}SLRD-Pad8)") (class "Default")
      (node (ref "IC1") (pin "8") (pinfunction "RDY0/SLRD_8") (pintype "input"))
    )
    (net (code "57") (name "unconnected-(IC1-RDY1{slash}SLRW-Pad9)") (class "Default")
      (node (ref "IC1") (pin "9") (pinfunction "RDY1/SLRW_9") (pintype "input"))
    )
    (net (code "58") (name "unconnected-(IC1-WAKEUP-Pad51)") (class "Default")
      (node (ref "IC1") (pin "51") (pinfunction "WAKEUP_51") (pintype "input"))
    )
    (net (code "59") (name "unconnected-(J1-PadGNDBREAK)") (class "Default")
      (node (ref "J1") (pin "GNDBREAK") (pinfunction "GNDBREAK_GNDBREAK") (pintype "bidirectional"))
    )
    (net (code "60") (name "unconnected-(PAR-Pad15)") (class "Default")
      (node (ref "PAR") (pin "15") (pinfunction "15_15") (pintype "passive"))
    )
    (net (code "61") (name "unconnected-(PAR-Pad19)") (class "Default")
      (node (ref "PAR") (pin "19") (pinfunction "19_19") (pintype "passive"))
    )
    (net (code "62") (name "unconnected-(U$1-LV-Pad6)") (class "Default")
      (node (ref "U$1") (pin "6") (pinfunction "LV_6") (pintype "bidirectional"))
    )
    (net (code "63") (name "unconnected-(U$1-OSC-Pad7)") (class "Default")
      (node (ref "U$1") (pin "7") (pinfunction "OSC_7") (pintype "bidirectional"))
    )
    (net (code "64") (name "unconnected-(U2-WDI-Pad4)") (class "Default")
      (node (ref "U2") (pin "4") (pinfunction "WDI_4") (pintype "bidirectional"))
    )
    (net (code "65") (name "unconnected-(X1-PadVBUS)") (class "Default")
      (node (ref "X1") (pin "VBUS") (pinfunction "VBUS_VBUS") (pintype "bidirectional"))
    )
  )
)
